# base_acacia.net
KiCad netlist of a schematic drawn in EAGLE
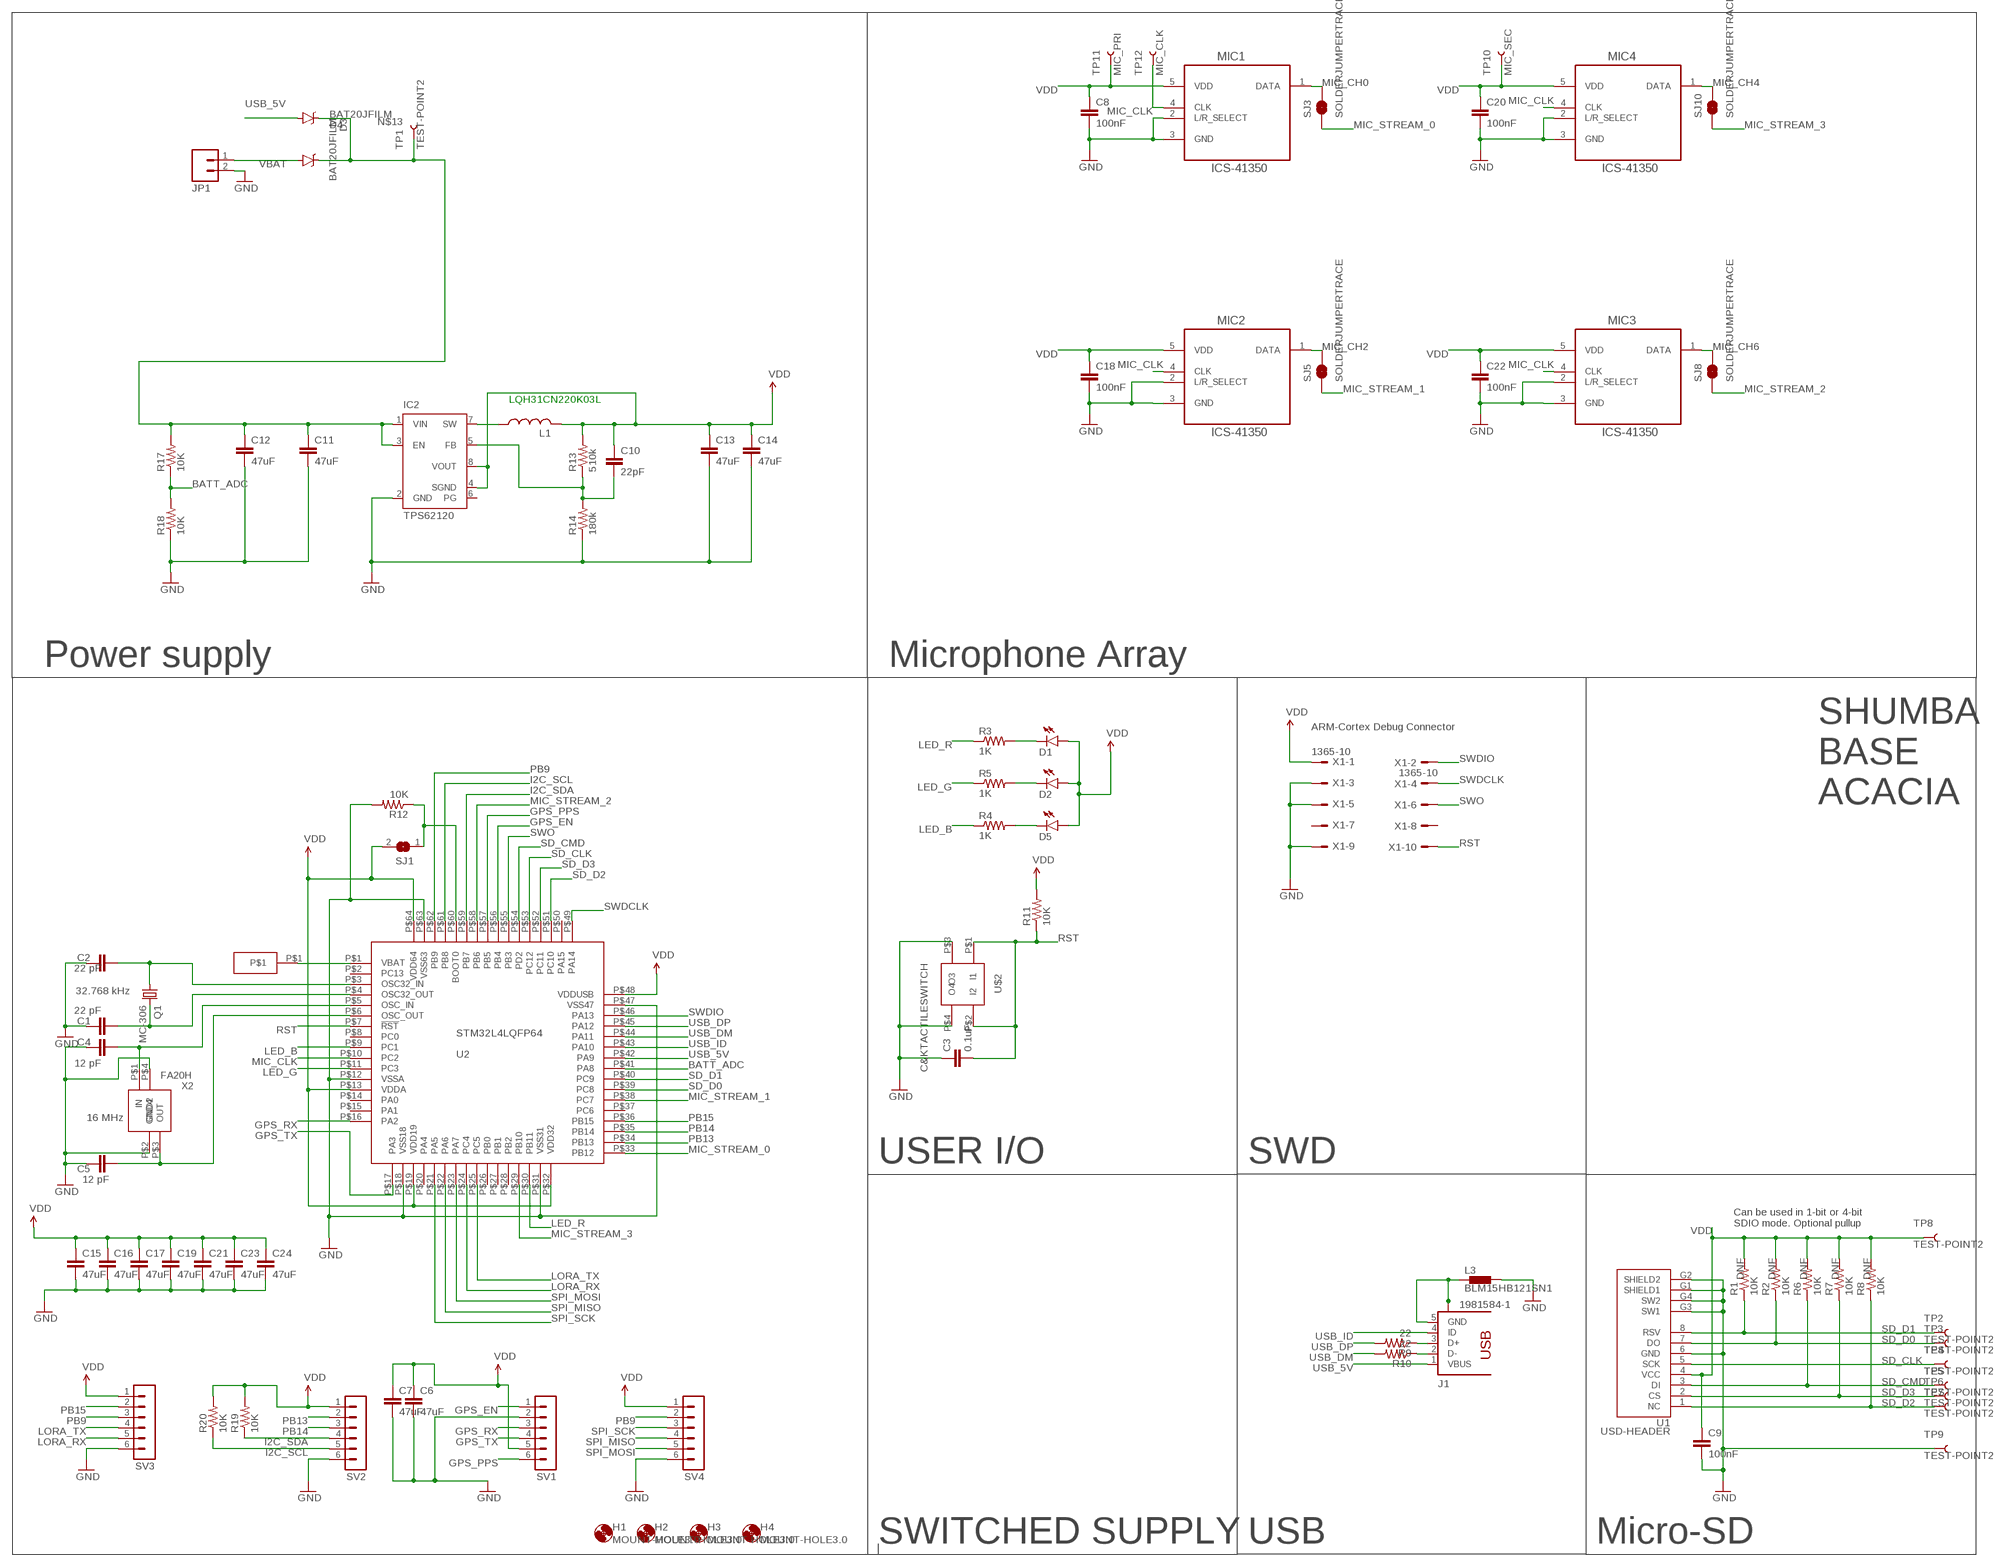
[diagram p0: schematic, sheet 1]

(export (version "E")
  (design (tool "Eeschema 10.0.6"))
  (components
    (comp (ref "C1")
      (value "22 pF")
      (footprint "eagle-import:0603-CAP")
      (libsource (lib "eagle-import") (part "CAP0603-CAP"))
    )
    (comp (ref "C2")
      (value "22 pF")
      (footprint "eagle-import:0603-CAP")
      (libsource (lib "eagle-import") (part "CAP0603-CAP"))
    )
    (comp (ref "C3")
      (value "0.1uF")
      (footprint "eagle-import:0603-CAP")
      (libsource (lib "eagle-import") (part "0.1UF-25V(+80/-20%)(0603)"))
    )
    (comp (ref "C4")
      (value "12 pF")
      (footprint "eagle-import:0603-CAP")
      (libsource (lib "eagle-import") (part "CAP0603-CAP"))
    )
    (comp (ref "C5")
      (value "12 pF")
      (footprint "eagle-import:0603-CAP")
      (libsource (lib "eagle-import") (part "CAP0603-CAP"))
    )
    (comp (ref "C6")
      (value "47uF")
      (footprint "eagle-import:0603-CAP")
      (libsource (lib "eagle-import") (part "SparkFun-Passives_CAP0603-CAP"))
    )
    (comp (ref "C7")
      (value "47uF")
      (footprint "eagle-import:0603-CAP")
      (libsource (lib "eagle-import") (part "SparkFun-Passives_CAP0603-CAP"))
    )
    (comp (ref "C8")
      (value "100nF")
      (footprint "eagle-import:0603-CAP")
      (libsource (lib "eagle-import") (part "SparkFun-Passives_CAP0603-CAP"))
    )
    (comp (ref "C9")
      (value "100nF")
      (footprint "eagle-import:0603-CAP")
      (libsource (lib "eagle-import") (part "SparkFun-Passives_CAP0603-CAP"))
    )
    (comp (ref "C10")
      (value "22pF")
      (footprint "eagle-import:0603-CAP")
      (libsource (lib "eagle-import") (part "SparkFun-Passives_CAP0603-CAP"))
    )
    (comp (ref "C11")
      (value "47uF")
      (footprint "eagle-import:0603-CAP")
      (libsource (lib "eagle-import") (part "SparkFun-Passives_CAP0603-CAP"))
    )
    (comp (ref "C12")
      (value "47uF")
      (footprint "eagle-import:0603-CAP")
      (libsource (lib "eagle-import") (part "SparkFun-Passives_CAP0603-CAP"))
    )
    (comp (ref "C13")
      (value "47uF")
      (footprint "eagle-import:0603-CAP")
      (libsource (lib "eagle-import") (part "SparkFun-Passives_CAP0603-CAP"))
    )
    (comp (ref "C14")
      (value "47uF")
      (footprint "eagle-import:0603-CAP")
      (libsource (lib "eagle-import") (part "SparkFun-Passives_CAP0603-CAP"))
    )
    (comp (ref "C15")
      (value "47uF")
      (footprint "eagle-import:0603-CAP")
      (libsource (lib "eagle-import") (part "SparkFun-Passives_CAP0603-CAP"))
    )
    (comp (ref "C16")
      (value "47uF")
      (footprint "eagle-import:0603-CAP")
      (libsource (lib "eagle-import") (part "SparkFun-Passives_CAP0603-CAP"))
    )
    (comp (ref "C17")
      (value "47uF")
      (footprint "eagle-import:0603-CAP")
      (libsource (lib "eagle-import") (part "SparkFun-Passives_CAP0603-CAP"))
    )
    (comp (ref "C18")
      (value "100nF")
      (footprint "eagle-import:0603-CAP")
      (libsource (lib "eagle-import") (part "SparkFun-Passives_CAP0603-CAP"))
    )
    (comp (ref "C19")
      (value "47uF")
      (footprint "eagle-import:0603-CAP")
      (libsource (lib "eagle-import") (part "SparkFun-Passives_CAP0603-CAP"))
    )
    (comp (ref "C20")
      (value "100nF")
      (footprint "eagle-import:0603-CAP")
      (libsource (lib "eagle-import") (part "SparkFun-Passives_CAP0603-CAP"))
    )
    (comp (ref "C21")
      (value "47uF")
      (footprint "eagle-import:0603-CAP")
      (libsource (lib "eagle-import") (part "SparkFun-Passives_CAP0603-CAP"))
    )
    (comp (ref "C22")
      (value "100nF")
      (footprint "eagle-import:0603-CAP")
      (libsource (lib "eagle-import") (part "SparkFun-Passives_CAP0603-CAP"))
    )
    (comp (ref "C23")
      (value "47uF")
      (footprint "eagle-import:0603-CAP")
      (libsource (lib "eagle-import") (part "SparkFun-Passives_CAP0603-CAP"))
    )
    (comp (ref "C24")
      (value "47uF")
      (footprint "eagle-import:0603-CAP")
      (libsource (lib "eagle-import") (part "SparkFun-Passives_CAP0603-CAP"))
    )
    (comp (ref "D1")
      (value "LED0603")
      (footprint "eagle-import:LED-0603")
      (libsource (lib "eagle-import") (part "LED0603"))
    )
    (comp (ref "D2")
      (value "LED0603")
      (footprint "eagle-import:LED-0603")
      (libsource (lib "eagle-import") (part "LED0603"))
    )
    (comp (ref "D3")
      (value "BAT20JFILM")
      (footprint "eagle-import:SOD-323")
      (libsource (lib "eagle-import") (part "BAT20JFILM"))
    )
    (comp (ref "D4")
      (value "BAT20JFILM")
      (footprint "eagle-import:SOD-323")
      (libsource (lib "eagle-import") (part "BAT20JFILM"))
    )
    (comp (ref "D5")
      (value "LED0603")
      (footprint "eagle-import:LED-0603")
      (libsource (lib "eagle-import") (part "LED0603"))
    )
    (comp (ref "H1")
      (value "MOUNT-HOLE3.0")
      (footprint "eagle-import:3,0")
      (libsource (lib "eagle-import") (part "MOUNT-HOLE3.0"))
    )
    (comp (ref "H2")
      (value "MOUNT-HOLE3.0")
      (footprint "eagle-import:3,0")
      (libsource (lib "eagle-import") (part "MOUNT-HOLE3.0"))
    )
    (comp (ref "H3")
      (value "MOUNT-HOLE3.0")
      (footprint "eagle-import:3,0")
      (libsource (lib "eagle-import") (part "MOUNT-HOLE3.0"))
    )
    (comp (ref "H4")
      (value "MOUNT-HOLE3.0")
      (footprint "eagle-import:3,0")
      (libsource (lib "eagle-import") (part "MOUNT-HOLE3.0"))
    )
    (comp (ref "IC2")
      (value "TPS62120")
      (footprint "eagle-import:DCN-R-PDSO-G8")
      (libsource (lib "eagle-import") (part "TPS62120"))
    )
    (comp (ref "J1")
      (value "1981584-1")
      (footprint "eagle-import:1981584-1")
      (fields (field (name "MF") "Hirose") (field (name "MPN") "ZX 62 B 5PA(33)"))
      (libsource (lib "eagle-import") (part "1981584-1"))
    )
    (comp (ref "JP1")
      (value "M02PTH4")
      (footprint "eagle-import:1X02_XTRA_BIG")
      (libsource (lib "eagle-import") (part "M02PTH4"))
    )
    (comp (ref "L1")
      (value "L-USL3216C")
      (footprint "eagle-import:L3216C")
      (libsource (lib "eagle-import") (part "L-USL3216C"))
    )
    (comp (ref "L3")
      (value "BLM15HB121SN1")
      (footprint "eagle-import:0402")
      (libsource (lib "eagle-import") (part "BLM15HB121SN1"))
    )
    (comp (ref "MIC1")
      (value "ICS-41350")
      (footprint "eagle-import:ADI_ADMP521A")
      (libsource (lib "eagle-import") (part "ICS-41350"))
    )
    (comp (ref "MIC2")
      (value "ICS-41350")
      (footprint "eagle-import:ADI_ADMP521A")
      (libsource (lib "eagle-import") (part "ICS-41350"))
    )
    (comp (ref "MIC3")
      (value "ICS-41350")
      (footprint "eagle-import:ADI_ADMP521A")
      (libsource (lib "eagle-import") (part "ICS-41350"))
    )
    (comp (ref "MIC4")
      (value "ICS-41350")
      (footprint "eagle-import:ADI_ADMP521A")
      (libsource (lib "eagle-import") (part "ICS-41350"))
    )
    (comp (ref "Q1")
      (value "MC-306")
      (footprint "eagle-import:MC-306")
      (fields
        (field (name "MPN") "MC-306 60.0KHZ  100PPM ,12.5PF")
        (field (name "MPN_1") "MC-306 32.768KHZ  20PPM ,12.5PF")
        (field (name "OC_FARNELL") "1216208")
      )
      (libsource (lib "eagle-import") (part "MC-306"))
    )
    (comp (ref "R1")
      (value "10K")
      (footprint "eagle-import:0603-RES")
      (fields (field (name "DNF") "DNF"))
      (libsource (lib "eagle-import") (part "10KOHM-1/10W-1%(0603)0603"))
    )
    (comp (ref "R2")
      (value "10K")
      (footprint "eagle-import:0603-RES")
      (fields (field (name "DNF") "DNF"))
      (libsource (lib "eagle-import") (part "10KOHM-1/10W-1%(0603)0603"))
    )
    (comp (ref "R3")
      (value "1K")
      (footprint "eagle-import:0603-RES")
      (libsource (lib "eagle-import") (part "1KOHM-1/10W-1%(0603)"))
    )
    (comp (ref "R4")
      (value "1K")
      (footprint "eagle-import:0603-RES")
      (libsource (lib "eagle-import") (part "1KOHM-1/10W-1%(0603)"))
    )
    (comp (ref "R5")
      (value "1K")
      (footprint "eagle-import:0603-RES")
      (libsource (lib "eagle-import") (part "1KOHM-1/10W-1%(0603)"))
    )
    (comp (ref "R6")
      (value "10K")
      (footprint "eagle-import:0603-RES")
      (fields (field (name "DNF") "DNF"))
      (libsource (lib "eagle-import") (part "10KOHM-1/10W-1%(0603)0603"))
    )
    (comp (ref "R7")
      (value "10K")
      (footprint "eagle-import:0603-RES")
      (fields (field (name "DNF") "DNF"))
      (libsource (lib "eagle-import") (part "10KOHM-1/10W-1%(0603)0603"))
    )
    (comp (ref "R8")
      (value "10K")
      (footprint "eagle-import:0603-RES")
      (fields (field (name "DNF") "DNF"))
      (libsource (lib "eagle-import") (part "10KOHM-1/10W-1%(0603)0603"))
    )
    (comp (ref "R9")
      (value "22")
      (footprint "eagle-import:0603-RES")
      (libsource (lib "eagle-import") (part "10KOHM-1/10W-1%(0603)0603"))
    )
    (comp (ref "R10")
      (value "22")
      (footprint "eagle-import:0603-RES")
      (libsource (lib "eagle-import") (part "10KOHM-1/10W-1%(0603)0603"))
    )
    (comp (ref "R11")
      (value "10K")
      (footprint "eagle-import:0603-RES")
      (libsource (lib "eagle-import") (part "10KOHM-1/10W-1%(0603)0603"))
    )
    (comp (ref "R12")
      (value "10K")
      (footprint "eagle-import:0603-RES")
      (libsource (lib "eagle-import") (part "10KOHM-1/10W-1%(0603)0603"))
    )
    (comp (ref "R13")
      (value "510k")
      (footprint "eagle-import:0603-RES")
      (libsource (lib "eagle-import") (part "10KOHM-1/10W-1%(0603)0603"))
    )
    (comp (ref "R14")
      (value "180k")
      (footprint "eagle-import:0603-RES")
      (libsource (lib "eagle-import") (part "10KOHM-1/10W-1%(0603)0603"))
    )
    (comp (ref "R17")
      (value "10K")
      (footprint "eagle-import:0603-RES")
      (libsource (lib "eagle-import") (part "10KOHM-1/10W-1%(0603)0603"))
    )
    (comp (ref "R18")
      (value "10K")
      (footprint "eagle-import:0603-RES")
      (libsource (lib "eagle-import") (part "10KOHM-1/10W-1%(0603)0603"))
    )
    (comp (ref "R19")
      (value "10K")
      (footprint "eagle-import:0603-RES")
      (libsource (lib "eagle-import") (part "10KOHM-1/10W-1%(0603)0603"))
    )
    (comp (ref "R20")
      (value "10K")
      (footprint "eagle-import:0603-RES")
      (libsource (lib "eagle-import") (part "10KOHM-1/10W-1%(0603)0603"))
    )
    (comp (ref "SJ1") (value "SJ") (footprint "eagle-import:SJ") (libsource (lib "eagle-import") (part "SJ")))
    (comp (ref "SJ3")
      (value "SOLDERJUMPERTRACE")
      (footprint "eagle-import:SJ_2S-TRACE")
      (libsource (lib "eagle-import") (part "SOLDERJUMPERTRACE"))
    )
    (comp (ref "SJ5")
      (value "SOLDERJUMPERTRACE")
      (footprint "eagle-import:SJ_2S-TRACE")
      (libsource (lib "eagle-import") (part "SOLDERJUMPERTRACE"))
    )
    (comp (ref "SJ8")
      (value "SOLDERJUMPERTRACE")
      (footprint "eagle-import:SJ_2S-TRACE")
      (libsource (lib "eagle-import") (part "SOLDERJUMPERTRACE"))
    )
    (comp (ref "SJ10")
      (value "SOLDERJUMPERTRACE")
      (footprint "eagle-import:SJ_2S-TRACE")
      (libsource (lib "eagle-import") (part "SOLDERJUMPERTRACE"))
    )
    (comp (ref "SV1")
      (value "MA06-1")
      (footprint "eagle-import:MA06-1")
      (libsource (lib "eagle-import") (part "MA06-1"))
    )
    (comp (ref "SV2")
      (value "MA06-1")
      (footprint "eagle-import:MA06-1")
      (libsource (lib "eagle-import") (part "MA06-1"))
    )
    (comp (ref "SV3")
      (value "MA06-1")
      (footprint "eagle-import:MA06-1")
      (libsource (lib "eagle-import") (part "MA06-1"))
    )
    (comp (ref "SV4")
      (value "MA06-1")
      (footprint "eagle-import:MA06-1")
      (libsource (lib "eagle-import") (part "MA06-1"))
    )
    (comp (ref "TP1")
      (value "TEST-POINT2")
      (footprint "eagle-import:PAD.02X.02")
      (libsource (lib "eagle-import") (part "TEST-POINT2"))
    )
    (comp (ref "TP2")
      (value "TEST-POINT2")
      (footprint "eagle-import:PAD.02X.02")
      (libsource (lib "eagle-import") (part "TEST-POINT2"))
    )
    (comp (ref "TP3")
      (value "TEST-POINT2")
      (footprint "eagle-import:PAD.02X.02")
      (libsource (lib "eagle-import") (part "TEST-POINT2"))
    )
    (comp (ref "TP4")
      (value "TEST-POINT2")
      (footprint "eagle-import:PAD.02X.02")
      (libsource (lib "eagle-import") (part "TEST-POINT2"))
    )
    (comp (ref "TP5")
      (value "TEST-POINT2")
      (footprint "eagle-import:PAD.02X.02")
      (libsource (lib "eagle-import") (part "TEST-POINT2"))
    )
    (comp (ref "TP6")
      (value "TEST-POINT2")
      (footprint "eagle-import:PAD.02X.02")
      (libsource (lib "eagle-import") (part "TEST-POINT2"))
    )
    (comp (ref "TP7")
      (value "TEST-POINT2")
      (footprint "eagle-import:PAD.02X.02")
      (libsource (lib "eagle-import") (part "TEST-POINT2"))
    )
    (comp (ref "TP8")
      (value "TEST-POINT2")
      (footprint "eagle-import:PAD.02X.02")
      (libsource (lib "eagle-import") (part "TEST-POINT2"))
    )
    (comp (ref "TP9")
      (value "TEST-POINT2")
      (footprint "eagle-import:PAD.02X.02")
      (libsource (lib "eagle-import") (part "TEST-POINT2"))
    )
    (comp (ref "TP10")
      (value "MIC_SEC")
      (footprint "eagle-import:PAD.02X.02")
      (libsource (lib "eagle-import") (part "TEST-POINT2"))
    )
    (comp (ref "TP11")
      (value "MIC_PRI")
      (footprint "eagle-import:PAD.02X.02")
      (libsource (lib "eagle-import") (part "TEST-POINT2"))
    )
    (comp (ref "TP12")
      (value "MIC_CLK")
      (footprint "eagle-import:PAD.02X.02")
      (libsource (lib "eagle-import") (part "TEST-POINT2"))
    )
    (comp (ref "U$2")
      (value "C&KTACTILESWITCH")
      (footprint "eagle-import:C&KTACTILESWITCH")
      (libsource (lib "eagle-import") (part "C&KTACTILESWITCH"))
    )
    (comp (ref "U$7")
      (value "SMDPAD")
      (footprint "eagle-import:SMDPAD")
      (libsource (lib "eagle-import") (part "SMDPAD"))
    )
    (comp (ref "U1")
      (value "USD-HEADER")
      (footprint "eagle-import:USD-HEADER-1.1")
      (libsource (lib "eagle-import") (part "USD-HEADER"))
    )
    (comp (ref "U2")
      (value "STM32L4LQFP64")
      (footprint "eagle-import:STM32L4LQFP64")
      (libsource (lib "eagle-import") (part "STM32L4LQFP64"))
    )
    (comp (ref "X1")
      (value "1365-10")
      (footprint "eagle-import:1365-10")
      (fields (field (name "SKU") "SHF-105-01-L-D-SM"))
      (libsource (lib "eagle-import") (part "1365-10"))
    )
    (comp (ref "X2")
      (value "FA20H")
      (footprint "eagle-import:FA-20H")
      (fields (field (name "MPN") "Q24FA20H00044 FA-20H 16 MHZ 9.0PF  Crystal, 16 MHz, SMD"))
      (libsource (lib "eagle-import") (part "FA20H"))
    )
  )
  (nets
    (net (code "1") (name "/BATT_ADC") (class "Default")
      (node (ref "R17") (pin "1") (pinfunction "1_1") (pintype "passive"))
      (node (ref "R18") (pin "2") (pinfunction "2_2") (pintype "passive"))
      (node (ref "U2") (pin "P$41") (pinfunction "PA8_P$41") (pintype "bidirectional"))
    )
    (net (code "2") (name "/GPS_EN") (class "Default")
      (node (ref "SV1") (pin "1") (pinfunction "1_1") (pintype "passive"))
      (node (ref "U2") (pin "P$56") (pinfunction "PB4_P$56") (pintype "bidirectional"))
    )
    (net (code "3") (name "/GPS_PPS") (class "Default")
      (node (ref "SV1") (pin "6") (pinfunction "6_6") (pintype "passive"))
      (node (ref "U2") (pin "P$57") (pinfunction "PB5_P$57") (pintype "bidirectional"))
    )
    (net (code "4") (name "/GPS_RX") (class "Default")
      (node (ref "SV1") (pin "3") (pinfunction "3_3") (pintype "passive"))
      (node (ref "U2") (pin "P$16") (pinfunction "PA2_P$16") (pintype "bidirectional"))
    )
    (net (code "5") (name "/GPS_TX") (class "Default")
      (node (ref "SV1") (pin "4") (pinfunction "4_4") (pintype "passive"))
      (node (ref "U2") (pin "P$17") (pinfunction "PA3_P$17") (pintype "bidirectional"))
    )
    (net (code "6") (name "/I2C_SCL") (class "Default")
      (node (ref "R20") (pin "1") (pinfunction "1_1") (pintype "passive"))
      (node (ref "SV2") (pin "5") (pinfunction "5_5") (pintype "passive"))
      (node (ref "U2") (pin "P$61") (pinfunction "PB8_P$61") (pintype "bidirectional"))
    )
    (net (code "7") (name "/I2C_SDA") (class "Default")
      (node (ref "R19") (pin "1") (pinfunction "1_1") (pintype "passive"))
      (node (ref "SV2") (pin "4") (pinfunction "4_4") (pintype "passive"))
      (node (ref "U2") (pin "P$59") (pinfunction "PB7_P$59") (pintype "bidirectional"))
    )
    (net (code "8") (name "/LED_B") (class "Default")
      (node (ref "R4") (pin "1") (pinfunction "1_1") (pintype "passive"))
      (node (ref "U2") (pin "P$9") (pinfunction "PC1_P$9") (pintype "bidirectional"))
    )
    (net (code "9") (name "/LED_G") (class "Default")
      (node (ref "R5") (pin "1") (pinfunction "1_1") (pintype "passive"))
      (node (ref "U2") (pin "P$11") (pinfunction "PC3_P$11") (pintype "bidirectional"))
    )
    (net (code "10") (name "/LED_R") (class "Default")
      (node (ref "R3") (pin "1") (pinfunction "1_1") (pintype "passive"))
      (node (ref "U2") (pin "P$30") (pinfunction "PB11_P$30") (pintype "bidirectional"))
    )
    (net (code "11") (name "/LORA_RX") (class "Default")
      (node (ref "SV3") (pin "5") (pinfunction "5_5") (pintype "passive"))
      (node (ref "U2") (pin "P$24") (pinfunction "PC4_P$24") (pintype "bidirectional"))
    )
    (net (code "12") (name "/LORA_TX") (class "Default")
      (node (ref "SV3") (pin "4") (pinfunction "4_4") (pintype "passive"))
      (node (ref "U2") (pin "P$25") (pinfunction "PC5_P$25") (pintype "bidirectional"))
    )
    (net (code "13") (name "/MIC_CH0") (class "Default")
      (node (ref "MIC1") (pin "1") (pinfunction "DATA_1") (pintype "output"))
      (node (ref "SJ3") (pin "2") (pinfunction "2_2") (pintype "passive"))
    )
    (net (code "14") (name "/MIC_CH2") (class "Default")
      (node (ref "MIC2") (pin "1") (pinfunction "DATA_1") (pintype "output"))
      (node (ref "SJ5") (pin "2") (pinfunction "2_2") (pintype "passive"))
    )
    (net (code "15") (name "/MIC_CH4") (class "Default")
      (node (ref "MIC4") (pin "1") (pinfunction "DATA_1") (pintype "output"))
      (node (ref "SJ10") (pin "2") (pinfunction "2_2") (pintype "passive"))
    )
    (net (code "16") (name "/MIC_CH6") (class "Default")
      (node (ref "MIC3") (pin "1") (pinfunction "DATA_1") (pintype "output"))
      (node (ref "SJ8") (pin "2") (pinfunction "2_2") (pintype "passive"))
    )
    (net (code "17") (name "/MIC_CLK") (class "Default")
      (node (ref "MIC1") (pin "4") (pinfunction "CLK_4") (pintype "input"))
      (node (ref "MIC2") (pin "4") (pinfunction "CLK_4") (pintype "input"))
      (node (ref "MIC3") (pin "4") (pinfunction "CLK_4") (pintype "input"))
      (node (ref "MIC4") (pin "4") (pinfunction "CLK_4") (pintype "input"))
      (node (ref "TP12") (pin "P$1") (pinfunction "1_P$1") (pintype "bidirectional"))
      (node (ref "U2") (pin "P$10") (pinfunction "PC2_P$10") (pintype "bidirectional"))
    )
    (net (code "18") (name "/MIC_STREAM_0") (class "Default")
      (node (ref "SJ3") (pin "1") (pinfunction "1_1") (pintype "passive"))
      (node (ref "U2") (pin "P$33") (pinfunction "PB12_P$33") (pintype "bidirectional"))
    )
    (net (code "19") (name "/MIC_STREAM_1") (class "Default")
      (node (ref "SJ5") (pin "1") (pinfunction "1_1") (pintype "passive"))
      (node (ref "U2") (pin "P$38") (pinfunction "PC7_P$38") (pintype "bidirectional"))
    )
    (net (code "20") (name "/MIC_STREAM_2") (class "Default")
      (node (ref "SJ8") (pin "1") (pinfunction "1_1") (pintype "passive"))
      (node (ref "U2") (pin "P$58") (pinfunction "PB6_P$58") (pintype "bidirectional"))
    )
    (net (code "21") (name "/MIC_STREAM_3") (class "Default")
      (node (ref "SJ10") (pin "1") (pinfunction "1_1") (pintype "passive"))
      (node (ref "U2") (pin "P$29") (pinfunction "PB10_P$29") (pintype "bidirectional"))
    )
    (net (code "22") (name "/N$13") (class "Default")
      (node (ref "C11") (pin "1") (pinfunction "1_1") (pintype "passive"))
      (node (ref "C12") (pin "1") (pinfunction "1_1") (pintype "passive"))
      (node (ref "D3") (pin "C") (pinfunction "C_C") (pintype "passive"))
      (node (ref "D4") (pin "C") (pinfunction "C_C") (pintype "passive"))
      (node (ref "IC2") (pin "1") (pinfunction "VIN_1") (pintype "input"))
      (node (ref "IC2") (pin "3") (pinfunction "EN_3") (pintype "input"))
      (node (ref "R17") (pin "2") (pinfunction "2_2") (pintype "passive"))
      (node (ref "TP1") (pin "P$1") (pinfunction "1_P$1") (pintype "bidirectional"))
    )
    (net (code "23") (name "/PB9") (class "Default")
      (node (ref "SV3") (pin "3") (pinfunction "3_3") (pintype "passive"))
      (node (ref "SV4") (pin "2") (pinfunction "2_2") (pintype "passive"))
      (node (ref "U2") (pin "P$62") (pinfunction "PB9_P$62") (pintype "bidirectional"))
    )
    (net (code "24") (name "/PB13") (class "Default")
      (node (ref "SV2") (pin "2") (pinfunction "2_2") (pintype "passive"))
      (node (ref "U2") (pin "P$34") (pinfunction "PB13_P$34") (pintype "bidirectional"))
    )
    (net (code "25") (name "/PB14") (class "Default")
      (node (ref "SV2") (pin "3") (pinfunction "3_3") (pintype "passive"))
      (node (ref "U2") (pin "P$35") (pinfunction "PB14_P$35") (pintype "bidirectional"))
    )
    (net (code "26") (name "/PB15") (class "Default")
      (node (ref "SV3") (pin "2") (pinfunction "2_2") (pintype "passive"))
      (node (ref "U2") (pin "P$36") (pinfunction "PB15_P$36") (pintype "bidirectional"))
    )
    (net (code "27") (name "/RST") (class "Default")
      (node (ref "C3") (pin "2") (pinfunction "2_2") (pintype "passive"))
      (node (ref "R11") (pin "1") (pinfunction "1_1") (pintype "passive"))
      (node (ref "U$2") (pin "P$1") (pinfunction "I1_P$1") (pintype "bidirectional"))
      (node (ref "U$2") (pin "P$2") (pinfunction "I2_P$2") (pintype "bidirectional"))
      (node (ref "U2") (pin "P$7") (pinfunction "~{RST}_P$7") (pintype "bidirectional"))
      (node (ref "X1") (pin "10") (pinfunction "S_10") (pintype "passive"))
    )
    (net (code "28") (name "/SD_CLK") (class "Default")
      (node (ref "TP4") (pin "P$1") (pinfunction "1_P$1") (pintype "bidirectional"))
      (node (ref "U1") (pin "5") (pinfunction "SCK_5") (pintype "bidirectional"))
      (node (ref "U2") (pin "P$53") (pinfunction "PC12_P$53") (pintype "bidirectional"))
    )
    (net (code "29") (name "/SD_CMD") (class "Default")
      (node (ref "R6") (pin "1") (pinfunction "1_1") (pintype "passive"))
      (node (ref "TP5") (pin "P$1") (pinfunction "1_P$1") (pintype "bidirectional"))
      (node (ref "U1") (pin "3") (pinfunction "DI_3") (pintype "bidirectional"))
      (node (ref "U2") (pin "P$54") (pinfunction "PD2_P$54") (pintype "bidirectional"))
    )
    (net (code "30") (name "/SD_D0") (class "Default")
      (node (ref "R2") (pin "1") (pinfunction "1_1") (pintype "passive"))
      (node (ref "TP3") (pin "P$1") (pinfunction "1_P$1") (pintype "bidirectional"))
      (node (ref "U1") (pin "7") (pinfunction "DO_7") (pintype "bidirectional"))
      (node (ref "U2") (pin "P$39") (pinfunction "PC8_P$39") (pintype "bidirectional"))
    )
    (net (code "31") (name "/SD_D1") (class "Default")
      (node (ref "R1") (pin "1") (pinfunction "1_1") (pintype "passive"))
      (node (ref "TP2") (pin "P$1") (pinfunction "1_P$1") (pintype "bidirectional"))
      (node (ref "U1") (pin "8") (pinfunction "RSV_8") (pintype "bidirectional"))
      (node (ref "U2") (pin "P$40") (pinfunction "PC9_P$40") (pintype "bidirectional"))
    )
    (net (code "32") (name "/SD_D2") (class "Default")
      (node (ref "R8") (pin "1") (pinfunction "1_1") (pintype "passive"))
      (node (ref "TP7") (pin "P$1") (pinfunction "1_P$1") (pintype "bidirectional"))
      (node (ref "U1") (pin "1") (pinfunction "NC_1") (pintype "bidirectional"))
      (node (ref "U2") (pin "P$51") (pinfunction "PC10_P$51") (pintype "bidirectional"))
    )
    (net (code "33") (name "/SD_D3") (class "Default")
      (node (ref "R7") (pin "1") (pinfunction "1_1") (pintype "passive"))
      (node (ref "TP6") (pin "P$1") (pinfunction "1_P$1") (pintype "bidirectional"))
      (node (ref "U1") (pin "2") (pinfunction "CS_2") (pintype "bidirectional"))
      (node (ref "U2") (pin "P$52") (pinfunction "PC11_P$52") (pintype "bidirectional"))
    )
    (net (code "34") (name "/SPI_MISO") (class "Default")
      (node (ref "SV4") (pin "4") (pinfunction "4_4") (pintype "passive"))
      (node (ref "U2") (pin "P$22") (pinfunction "PA6_P$22") (pintype "bidirectional"))
    )
    (net (code "35") (name "/SPI_MOSI") (class "Default")
      (node (ref "SV4") (pin "5") (pinfunction "5_5") (pintype "passive"))
      (node (ref "U2") (pin "P$23") (pinfunction "PA7_P$23") (pintype "bidirectional"))
    )
    (net (code "36") (name "/SPI_SCK") (class "Default")
      (node (ref "SV4") (pin "3") (pinfunction "3_3") (pintype "passive"))
      (node (ref "U2") (pin "P$21") (pinfunction "PA5_P$21") (pintype "bidirectional"))
    )
    (net (code "37") (name "/SWDCLK") (class "Default")
      (node (ref "U2") (pin "P$49") (pinfunction "PA14_P$49") (pintype "bidirectional"))
      (node (ref "X1") (pin "4") (pinfunction "S_4") (pintype "passive"))
    )
    (net (code "38") (name "/SWDIO") (class "Default")
      (node (ref "U2") (pin "P$46") (pinfunction "PA13_P$46") (pintype "bidirectional"))
      (node (ref "X1") (pin "2") (pinfunction "S_2") (pintype "passive"))
    )
    (net (code "39") (name "/SWO") (class "Default")
      (node (ref "U2") (pin "P$55") (pinfunction "PB3_P$55") (pintype "bidirectional"))
      (node (ref "X1") (pin "6") (pinfunction "S_6") (pintype "passive"))
    )
    (net (code "40") (name "/USB_5V") (class "Default")
      (node (ref "D4") (pin "A") (pinfunction "A_A") (pintype "passive"))
      (node (ref "J1") (pin "1") (pinfunction "VBUS_1") (pintype "passive"))
      (node (ref "U2") (pin "P$42") (pinfunction "PA9_P$42") (pintype "bidirectional"))
    )
    (net (code "41") (name "/USB_DM") (class "Default")
      (node (ref "R10") (pin "2") (pinfunction "2_2") (pintype "passive"))
      (node (ref "U2") (pin "P$44") (pinfunction "PA11_P$44") (pintype "bidirectional"))
    )
    (net (code "42") (name "/USB_DP") (class "Default")
      (node (ref "R9") (pin "2") (pinfunction "2_2") (pintype "passive"))
      (node (ref "U2") (pin "P$45") (pinfunction "PA12_P$45") (pintype "bidirectional"))
    )
    (net (code "43") (name "/USB_ID") (class "Default")
      (node (ref "J1") (pin "4") (pinfunction "ID_4") (pintype "passive"))
      (node (ref "U2") (pin "P$43") (pinfunction "PA10_P$43") (pintype "bidirectional"))
    )
    (net (code "44") (name "/VBAT") (class "Default")
      (node (ref "D3") (pin "A") (pinfunction "A_A") (pintype "passive"))
      (node (ref "JP1") (pin "1") (pinfunction "1_1") (pintype "passive"))
    )
    (net (code "45") (name "GND") (class "Default")
      (node (ref "C1") (pin "1") (pinfunction "1_1") (pintype "passive"))
      (node (ref "C11") (pin "2") (pinfunction "2_2") (pintype "passive"))
      (node (ref "C12") (pin "2") (pinfunction "2_2") (pintype "passive"))
      (node (ref "C13") (pin "2") (pinfunction "2_2") (pintype "passive"))
      (node (ref "C14") (pin "2") (pinfunction "2_2") (pintype "passive"))
      (node (ref "C15") (pin "2") (pinfunction "2_2") (pintype "passive"))
      (node (ref "C16") (pin "2") (pinfunction "2_2") (pintype "passive"))
      (node (ref "C17") (pin "2") (pinfunction "2_2") (pintype "passive"))
      (node (ref "C18") (pin "2") (pinfunction "2_2") (pintype "passive"))
      (node (ref "C19") (pin "2") (pinfunction "2_2") (pintype "passive"))
      (node (ref "C2") (pin "1") (pinfunction "1_1") (pintype "passive"))
      (node (ref "C20") (pin "2") (pinfunction "2_2") (pintype "passive"))
      (node (ref "C21") (pin "2") (pinfunction "2_2") (pintype "passive"))
      (node (ref "C22") (pin "2") (pinfunction "2_2") (pintype "passive"))
      (node (ref "C23") (pin "2") (pinfunction "2_2") (pintype "passive"))
      (node (ref "C24") (pin "2") (pinfunction "2_2") (pintype "passive"))
      (node (ref "C3") (pin "1") (pinfunction "1_1") (pintype "passive"))
      (node (ref "C4") (pin "1") (pinfunction "1_1") (pintype "passive"))
      (node (ref "C5") (pin "1") (pinfunction "1_1") (pintype "passive"))
      (node (ref "C6") (pin "2") (pinfunction "2_2") (pintype "passive"))
      (node (ref "C7") (pin "2") (pinfunction "2_2") (pintype "passive"))
      (node (ref "C8") (pin "2") (pinfunction "2_2") (pintype "passive"))
      (node (ref "C9") (pin "2") (pinfunction "2_2") (pintype "passive"))
      (node (ref "IC2") (pin "2") (pinfunction "GND_2") (pintype "power_in"))
      (node (ref "JP1") (pin "2") (pinfunction "2_2") (pintype "passive"))
      (node (ref "L3") (pin "2") (pinfunction "2_2") (pintype "passive"))
      (node (ref "MIC1") (pin "2") (pinfunction "L/R_SELECT_2") (pintype "passive"))
      (node (ref "MIC1") (pin "3") (pinfunction "GND_3") (pintype "passive"))
      (node (ref "MIC2") (pin "2") (pinfunction "L/R_SELECT_2") (pintype "passive"))
      (node (ref "MIC2") (pin "3") (pinfunction "GND_3") (pintype "passive"))
      (node (ref "MIC3") (pin "2") (pinfunction "L/R_SELECT_2") (pintype "passive"))
      (node (ref "MIC3") (pin "3") (pinfunction "GND_3") (pintype "passive"))
      (node (ref "MIC4") (pin "2") (pinfunction "L/R_SELECT_2") (pintype "passive"))
      (node (ref "MIC4") (pin "3") (pinfunction "GND_3") (pintype "passive"))
      (node (ref "R12") (pin "2") (pinfunction "2_2") (pintype "passive"))
      (node (ref "R14") (pin "1") (pinfunction "1_1") (pintype "passive"))
      (node (ref "R18") (pin "1") (pinfunction "1_1") (pintype "passive"))
      (node (ref "SV1") (pin "2") (pinfunction "2_2") (pintype "passive"))
      (node (ref "SV2") (pin "6") (pinfunction "6_6") (pintype "passive"))
      (node (ref "SV3") (pin "6") (pinfunction "6_6") (pintype "passive"))
      (node (ref "SV4") (pin "6") (pinfunction "6_6") (pintype "passive"))
      (node (ref "TP9") (pin "P$1") (pinfunction "1_P$1") (pintype "bidirectional"))
      (node (ref "U$2") (pin "P$3") (pinfunction "O3_P$3") (pintype "bidirectional"))
      (node (ref "U$2") (pin "P$4") (pinfunction "O4_P$4") (pintype "bidirectional"))
      (node (ref "U1") (pin "6") (pinfunction "GND_6") (pintype "bidirectional"))
      (node (ref "U1") (pin "G1") (pinfunction "SHIELD1_G1") (pintype "bidirectional"))
      (node (ref "U1") (pin "G2") (pinfunction "SHIELD2_G2") (pintype "bidirectional"))
      (node (ref "U1") (pin "G3") (pinfunction "SW1_G3") (pintype "bidirectional"))
      (node (ref "U1") (pin "G4") (pinfunction "SW2_G4") (pintype "bidirectional"))
      (node (ref "U2") (pin "P$12") (pinfunction "VSSA_P$12") (pintype "power_in"))
      (node (ref "U2") (pin "P$18") (pinfunction "VSS18_P$18") (pintype "power_in"))
      (node (ref "U2") (pin "P$31") (pinfunction "VSS31_P$31") (pintype "power_in"))
      (node (ref "U2") (pin "P$47") (pinfunction "VSS47_P$47") (pintype "power_in"))
      (node (ref "U2") (pin "P$63") (pinfunction "VSS63_P$63") (pintype "power_in"))
      (node (ref "X1") (pin "3") (pinfunction "S_3") (pintype "passive"))
      (node (ref "X1") (pin "5") (pinfunction "S_5") (pintype "passive"))
      (node (ref "X1") (pin "9") (pinfunction "S_9") (pintype "passive"))
      (node (ref "X2") (pin "P$2") (pinfunction "GND2_P$2") (pintype "bidirectional"))
      (node (ref "X2") (pin "P$4") (pinfunction "GND4_P$4") (pintype "bidirectional"))
    )
    (net (code "46") (name "Net-(D1-PadC)") (class "Default")
      (node (ref "D1") (pin "C") (pinfunction "C_C") (pintype "passive"))
      (node (ref "R3") (pin "2") (pinfunction "2_2") (pintype "passive"))
    )
    (net (code "47") (name "Net-(D2-PadC)") (class "Default")
      (node (ref "D2") (pin "C") (pinfunction "C_C") (pintype "passive"))
      (node (ref "R5") (pin "2") (pinfunction "2_2") (pintype "passive"))
    )
    (net (code "48") (name "Net-(D5-PadC)") (class "Default")
      (node (ref "D5") (pin "C") (pinfunction "C_C") (pintype "passive"))
      (node (ref "R4") (pin "2") (pinfunction "2_2") (pintype "passive"))
    )
    (net (code "49") (name "Net-(IC2-FB)") (class "Default")
      (node (ref "C10") (pin "2") (pinfunction "2_2") (pintype "passive"))
      (node (ref "IC2") (pin "5") (pinfunction "FB_5") (pintype "input"))
      (node (ref "R13") (pin "1") (pinfunction "1_1") (pintype "passive"))
      (node (ref "R14") (pin "2") (pinfunction "2_2") (pintype "passive"))
    )
    (net (code "50") (name "Net-(IC2-SW)") (class "Default")
      (node (ref "IC2") (pin "7") (pinfunction "SW_7") (pintype "output"))
      (node (ref "L1") (pin "1") (pinfunction "1_1") (pintype "passive"))
    )
    (net (code "51") (name "Net-(J1-D+)") (class "Default")
      (node (ref "J1") (pin "3") (pinfunction "D+_3") (pintype "passive"))
      (node (ref "R9") (pin "1") (pinfunction "1_1") (pintype "passive"))
    )
    (net (code "52") (name "Net-(J1-D-)") (class "Default")
      (node (ref "J1") (pin "2") (pinfunction "D-_2") (pintype "passive"))
      (node (ref "R10") (pin "1") (pinfunction "1_1") (pintype "passive"))
    )
    (net (code "53") (name "Net-(J1-GND)") (class "Default")
      (node (ref "J1") (pin "5") (pinfunction "GND_5") (pintype "passive"))
      (node (ref "J1") (pin "S1") (pinfunction "S1_S1") (pintype "passive"))
      (node (ref "J1") (pin "S2") (pinfunction "S2_S2") (pintype "passive"))
      (node (ref "J1") (pin "S3") (pinfunction "S3_S3") (pintype "passive"))
      (node (ref "J1") (pin "S4") (pinfunction "S4_S4") (pintype "passive"))
      (node (ref "L3") (pin "1") (pinfunction "1_1") (pintype "passive"))
    )
    (net (code "54") (name "Net-(Q1-2)") (class "Default")
      (node (ref "C1") (pin "2") (pinfunction "2_2") (pintype "passive"))
      (node (ref "Q1") (pin "4") (pinfunction "2_4") (pintype "passive"))
      (node (ref "U2") (pin "P$4") (pinfunction "OSC32_OUT_P$4") (pintype "bidirectional"))
    )
    (net (code "55") (name "Net-(U2-BOOT0)") (class "Default")
      (node (ref "R12") (pin "1") (pinfunction "1_1") (pintype "passive"))
      (node (ref "SJ1") (pin "1") (pinfunction "1_1") (pintype "passive"))
      (node (ref "U2") (pin "P$60") (pinfunction "BOOT0_P$60") (pintype "bidirectional"))
    )
    (net (code "56") (name "Net-(U2-OSC32_IN)") (class "Default")
      (node (ref "C2") (pin "2") (pinfunction "2_2") (pintype "passive"))
      (node (ref "Q1") (pin "1") (pinfunction "1_1") (pintype "passive"))
      (node (ref "U2") (pin "P$3") (pinfunction "OSC32_IN_P$3") (pintype "bidirectional"))
    )
    (net (code "57") (name "Net-(U2-OSC_IN)") (class "Default")
      (node (ref "C4") (pin "2") (pinfunction "2_2") (pintype "passive"))
      (node (ref "U2") (pin "P$5") (pinfunction "OSC_IN_P$5") (pintype "bidirectional"))
      (node (ref "X2") (pin "P$1") (pinfunction "IN_P$1") (pintype "bidirectional"))
    )
    (net (code "58") (name "Net-(U2-OSC_OUT)") (class "Default")
      (node (ref "C5") (pin "2") (pinfunction "2_2") (pintype "passive"))
      (node (ref "U2") (pin "P$6") (pinfunction "OSC_OUT_P$6") (pintype "bidirectional"))
      (node (ref "X2") (pin "P$3") (pinfunction "OUT_P$3") (pintype "bidirectional"))
    )
    (net (code "59") (name "Net-(U2-VBAT)") (class "Default")
      (node (ref "U$7") (pin "P$1") (pinfunction "P$1_P$1") (pintype "bidirectional"))
      (node (ref "U2") (pin "P$1") (pinfunction "VBAT_P$1") (pintype "power_in"))
    )
    (net (code "60") (name "VDD") (class "Default")
      (node (ref "C10") (pin "1") (pinfunction "1_1") (pintype "passive"))
      (node (ref "C13") (pin "1") (pinfunction "1_1") (pintype "passive"))
      (node (ref "C14") (pin "1") (pinfunction "1_1") (pintype "passive"))
      (node (ref "C15") (pin "1") (pinfunction "1_1") (pintype "passive"))
      (node (ref "C16") (pin "1") (pinfunction "1_1") (pintype "passive"))
      (node (ref "C17") (pin "1") (pinfunction "1_1") (pintype "passive"))
      (node (ref "C18") (pin "1") (pinfunction "1_1") (pintype "passive"))
      (node (ref "C19") (pin "1") (pinfunction "1_1") (pintype "passive"))
      (node (ref "C20") (pin "1") (pinfunction "1_1") (pintype "passive"))
      (node (ref "C21") (pin "1") (pinfunction "1_1") (pintype "passive"))
      (node (ref "C22") (pin "1") (pinfunction "1_1") (pintype "passive"))
      (node (ref "C23") (pin "1") (pinfunction "1_1") (pintype "passive"))
      (node (ref "C24") (pin "1") (pinfunction "1_1") (pintype "passive"))
      (node (ref "C6") (pin "1") (pinfunction "1_1") (pintype "passive"))
      (node (ref "C7") (pin "1") (pinfunction "1_1") (pintype "passive"))
      (node (ref "C8") (pin "1") (pinfunction "1_1") (pintype "passive"))
      (node (ref "C9") (pin "1") (pinfunction "1_1") (pintype "passive"))
      (node (ref "D1") (pin "A") (pinfunction "A_A") (pintype "passive"))
      (node (ref "D2") (pin "A") (pinfunction "A_A") (pintype "passive"))
      (node (ref "D5") (pin "A") (pinfunction "A_A") (pintype "passive"))
      (node (ref "IC2") (pin "4") (pinfunction "SGND_4") (pintype "passive"))
      (node (ref "IC2") (pin "8") (pinfunction "VOUT_8") (pintype "output"))
      (node (ref "L1") (pin "2") (pinfunction "2_2") (pintype "passive"))
      (node (ref "MIC1") (pin "5") (pinfunction "VDD_5") (pintype "power_in"))
      (node (ref "MIC2") (pin "5") (pinfunction "VDD_5") (pintype "power_in"))
      (node (ref "MIC3") (pin "5") (pinfunction "VDD_5") (pintype "power_in"))
      (node (ref "MIC4") (pin "5") (pinfunction "VDD_5") (pintype "power_in"))
      (node (ref "R1") (pin "2") (pinfunction "2_2") (pintype "passive"))
      (node (ref "R11") (pin "2") (pinfunction "2_2") (pintype "passive"))
      (node (ref "R13") (pin "2") (pinfunction "2_2") (pintype "passive"))
      (node (ref "R19") (pin "2") (pinfunction "2_2") (pintype "passive"))
      (node (ref "R2") (pin "2") (pinfunction "2_2") (pintype "passive"))
      (node (ref "R20") (pin "2") (pinfunction "2_2") (pintype "passive"))
      (node (ref "R6") (pin "2") (pinfunction "2_2") (pintype "passive"))
      (node (ref "R7") (pin "2") (pinfunction "2_2") (pintype "passive"))
      (node (ref "R8") (pin "2") (pinfunction "2_2") (pintype "passive"))
      (node (ref "SJ1") (pin "2") (pinfunction "2_2") (pintype "passive"))
      (node (ref "SV1") (pin "5") (pinfunction "5_5") (pintype "passive"))
      (node (ref "SV2") (pin "1") (pinfunction "1_1") (pintype "passive"))
      (node (ref "SV3") (pin "1") (pinfunction "1_1") (pintype "passive"))
      (node (ref "SV4") (pin "1") (pinfunction "1_1") (pintype "passive"))
      (node (ref "TP10") (pin "P$1") (pinfunction "1_P$1") (pintype "bidirectional"))
      (node (ref "TP11") (pin "P$1") (pinfunction "1_P$1") (pintype "bidirectional"))
      (node (ref "TP8") (pin "P$1") (pinfunction "1_P$1") (pintype "bidirectional"))
      (node (ref "U1") (pin "4") (pinfunction "VCC_4") (pintype "bidirectional"))
      (node (ref "U2") (pin "P$13") (pinfunction "VDDA_P$13") (pintype "power_in"))
      (node (ref "U2") (pin "P$19") (pinfunction "VDD19_P$19") (pintype "power_in"))
      (node (ref "U2") (pin "P$32") (pinfunction "VDD32_P$32") (pintype "power_in"))
      (node (ref "U2") (pin "P$48") (pinfunction "VDDUSB_P$48") (pintype "power_in"))
      (node (ref "U2") (pin "P$64") (pinfunction "VDD64_P$64") (pintype "power_in"))
      (node (ref "X1") (pin "1") (pinfunction "S_1") (pintype "passive"))
    )
    (net (code "61") (name "unconnected-(IC2-PG-Pad6)") (class "Default")
      (node (ref "IC2") (pin "6") (pinfunction "PG_6") (pintype "passive"))
    )
    (net (code "62") (name "unconnected-(U2-PA0-PadP$14)") (class "Default")
      (node (ref "U2") (pin "P$14") (pinfunction "PA0_P$14") (pintype "bidirectional"))
    )
    (net (code "63") (name "unconnected-(U2-PA1-PadP$15)") (class "Default")
      (node (ref "U2") (pin "P$15") (pinfunction "PA1_P$15") (pintype "bidirectional"))
    )
    (net (code "64") (name "unconnected-(U2-PA4-PadP$20)") (class "Default")
      (node (ref "U2") (pin "P$20") (pinfunction "PA4_P$20") (pintype "bidirectional"))
    )
    (net (code "65") (name "unconnected-(U2-PA15-PadP$50)") (class "Default")
      (node (ref "U2") (pin "P$50") (pinfunction "PA15_P$50") (pintype "bidirectional"))
    )
    (net (code "66") (name "unconnected-(U2-PB0-PadP$26)") (class "Default")
      (node (ref "U2") (pin "P$26") (pinfunction "PB0_P$26") (pintype "bidirectional"))
    )
    (net (code "67") (name "unconnected-(U2-PB1-PadP$27)") (class "Default")
      (node (ref "U2") (pin "P$27") (pinfunction "PB1_P$27") (pintype "bidirectional"))
    )
    (net (code "68") (name "unconnected-(U2-PB2-PadP$28)") (class "Default")
      (node (ref "U2") (pin "P$28") (pinfunction "PB2_P$28") (pintype "bidirectional"))
    )
    (net (code "69") (name "unconnected-(U2-PC0-PadP$8)") (class "Default")
      (node (ref "U2") (pin "P$8") (pinfunction "PC0_P$8") (pintype "bidirectional"))
    )
    (net (code "70") (name "unconnected-(U2-PC6-PadP$37)") (class "Default")
      (node (ref "U2") (pin "P$37") (pinfunction "PC6_P$37") (pintype "bidirectional"))
    )
    (net (code "71") (name "unconnected-(U2-PC13-PadP$2)") (class "Default")
      (node (ref "U2") (pin "P$2") (pinfunction "PC13_P$2") (pintype "bidirectional"))
    )
    (net (code "72") (name "unconnected-(X1H-S-Pad7)") (class "Default")
      (node (ref "X1") (pin "7") (pinfunction "S_7") (pintype "passive"))
    )
    (net (code "73") (name "unconnected-(X1I-S-Pad8)") (class "Default")
      (node (ref "X1") (pin "8") (pinfunction "S_8") (pintype "passive"))
    )
  )
)
